# TXB0108PWR.net
KiCad netlist of a schematic drawn in EAGLE
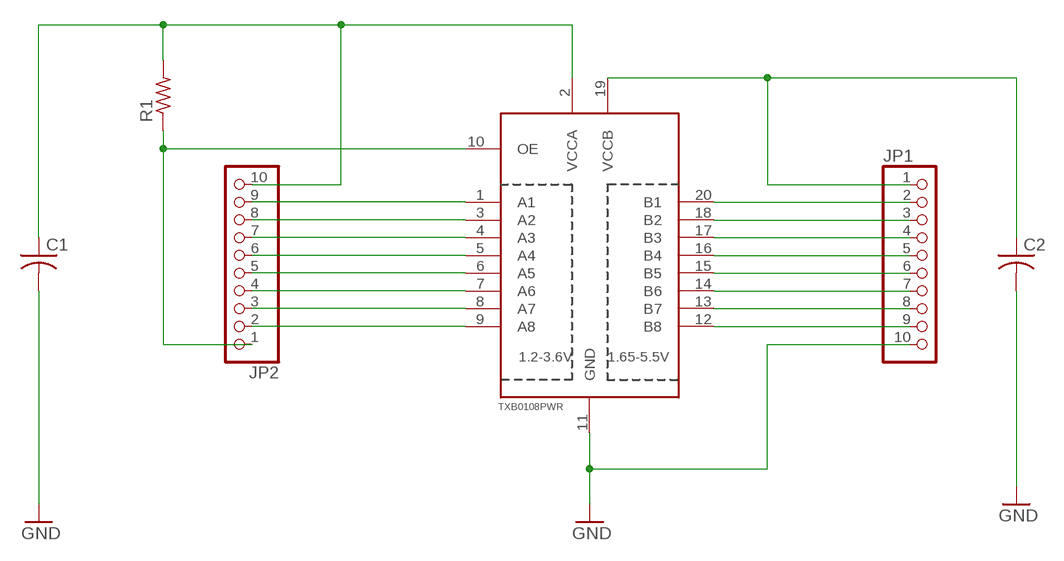
[diagram p0: schematic, sheet 1]

(export (version "E")
  (design (tool "Eeschema 10.0.6"))
  (components
    (comp (ref "C1")
      (value "C-USC0603")
      (footprint "eagle-import:C0603")
      (libsource (lib "eagle-import") (part "C-USC0603"))
    )
    (comp (ref "C2")
      (value "C-USC0603")
      (footprint "eagle-import:C0603")
      (libsource (lib "eagle-import") (part "C-USC0603"))
    )
    (comp (ref "JP1")
      (value "PINHD-1X10")
      (footprint "eagle-import:1X10")
      (libsource (lib "eagle-import") (part "PINHD-1X10"))
    )
    (comp (ref "JP2")
      (value "PINHD-1X10")
      (footprint "eagle-import:1X10")
      (libsource (lib "eagle-import") (part "PINHD-1X10"))
    )
    (comp (ref "R1")
      (value "R-US_R0603")
      (footprint "eagle-import:R0603")
      (libsource (lib "eagle-import") (part "R-US_R0603"))
    )
    (comp (ref "U$1")
      (value "TXB0108PWR")
      (footprint "eagle-import:TXB0108PWR")
      (libsource (lib "eagle-import") (part "TXB0108PWR"))
    )
  )
  (nets
    (net (code "1") (name "GND") (class "Default")
      (node (ref "C1") (pin "2") (pinfunction "2_2") (pintype "passive"))
      (node (ref "C2") (pin "2") (pinfunction "2_2") (pintype "passive"))
      (node (ref "JP1") (pin "10") (pinfunction "10_10") (pintype "passive"))
      (node (ref "U$1") (pin "11") (pinfunction "GND_11") (pintype "bidirectional"))
    )
    (net (code "2") (name "Net-(U$1-A1)") (class "Default")
      (node (ref "JP2") (pin "9") (pinfunction "9_9") (pintype "passive"))
      (node (ref "U$1") (pin "1") (pinfunction "A1_1") (pintype "bidirectional"))
    )
    (net (code "3") (name "Net-(U$1-A2)") (class "Default")
      (node (ref "JP2") (pin "8") (pinfunction "8_8") (pintype "passive"))
      (node (ref "U$1") (pin "3") (pinfunction "A2_3") (pintype "bidirectional"))
    )
    (net (code "4") (name "Net-(U$1-A3)") (class "Default")
      (node (ref "JP2") (pin "7") (pinfunction "7_7") (pintype "passive"))
      (node (ref "U$1") (pin "4") (pinfunction "A3_4") (pintype "bidirectional"))
    )
    (net (code "5") (name "Net-(U$1-A4)") (class "Default")
      (node (ref "JP2") (pin "6") (pinfunction "6_6") (pintype "passive"))
      (node (ref "U$1") (pin "5") (pinfunction "A4_5") (pintype "bidirectional"))
    )
    (net (code "6") (name "Net-(U$1-A5)") (class "Default")
      (node (ref "JP2") (pin "5") (pinfunction "5_5") (pintype "passive"))
      (node (ref "U$1") (pin "6") (pinfunction "A5_6") (pintype "bidirectional"))
    )
    (net (code "7") (name "Net-(U$1-A6)") (class "Default")
      (node (ref "JP2") (pin "4") (pinfunction "4_4") (pintype "passive"))
      (node (ref "U$1") (pin "7") (pinfunction "A6_7") (pintype "bidirectional"))
    )
    (net (code "8") (name "Net-(U$1-A7)") (class "Default")
      (node (ref "JP2") (pin "3") (pinfunction "3_3") (pintype "passive"))
      (node (ref "U$1") (pin "8") (pinfunction "A7_8") (pintype "bidirectional"))
    )
    (net (code "9") (name "Net-(U$1-A8)") (class "Default")
      (node (ref "JP2") (pin "2") (pinfunction "2_2") (pintype "passive"))
      (node (ref "U$1") (pin "9") (pinfunction "A8_9") (pintype "bidirectional"))
    )
    (net (code "10") (name "Net-(U$1-B1)") (class "Default")
      (node (ref "JP1") (pin "2") (pinfunction "2_2") (pintype "passive"))
      (node (ref "U$1") (pin "20") (pinfunction "B1_20") (pintype "bidirectional"))
    )
    (net (code "11") (name "Net-(U$1-B2)") (class "Default")
      (node (ref "JP1") (pin "3") (pinfunction "3_3") (pintype "passive"))
      (node (ref "U$1") (pin "18") (pinfunction "B2_18") (pintype "bidirectional"))
    )
    (net (code "12") (name "Net-(U$1-B3)") (class "Default")
      (node (ref "JP1") (pin "4") (pinfunction "4_4") (pintype "passive"))
      (node (ref "U$1") (pin "17") (pinfunction "B3_17") (pintype "bidirectional"))
    )
    (net (code "13") (name "Net-(U$1-B4)") (class "Default")
      (node (ref "JP1") (pin "5") (pinfunction "5_5") (pintype "passive"))
      (node (ref "U$1") (pin "16") (pinfunction "B4_16") (pintype "bidirectional"))
    )
    (net (code "14") (name "Net-(U$1-B5)") (class "Default")
      (node (ref "JP1") (pin "6") (pinfunction "6_6") (pintype "passive"))
      (node (ref "U$1") (pin "15") (pinfunction "B5_15") (pintype "bidirectional"))
    )
    (net (code "15") (name "Net-(U$1-B6)") (class "Default")
      (node (ref "JP1") (pin "7") (pinfunction "7_7") (pintype "passive"))
      (node (ref "U$1") (pin "14") (pinfunction "B6_14") (pintype "bidirectional"))
    )
    (net (code "16") (name "Net-(U$1-B7)") (class "Default")
      (node (ref "JP1") (pin "8") (pinfunction "8_8") (pintype "passive"))
      (node (ref "U$1") (pin "13") (pinfunction "B7_13") (pintype "bidirectional"))
    )
    (net (code "17") (name "Net-(U$1-B8)") (class "Default")
      (node (ref "JP1") (pin "9") (pinfunction "9_9") (pintype "passive"))
      (node (ref "U$1") (pin "12") (pinfunction "B8_12") (pintype "bidirectional"))
    )
    (net (code "18") (name "Net-(U$1-OE)") (class "Default")
      (node (ref "JP2") (pin "1") (pinfunction "1_1") (pintype "passive"))
      (node (ref "R1") (pin "1") (pinfunction "1_1") (pintype "passive"))
      (node (ref "U$1") (pin "10") (pinfunction "OE_10") (pintype "bidirectional"))
    )
    (net (code "19") (name "Net-(U$1-VCCA)") (class "Default")
      (node (ref "C1") (pin "1") (pinfunction "1_1") (pintype "passive"))
      (node (ref "JP2") (pin "10") (pinfunction "10_10") (pintype "passive"))
      (node (ref "R1") (pin "2") (pinfunction "2_2") (pintype "passive"))
      (node (ref "U$1") (pin "2") (pinfunction "VCCA_2") (pintype "bidirectional"))
    )
    (net (code "20") (name "Net-(U$1-VCCB)") (class "Default")
      (node (ref "C2") (pin "1") (pinfunction "1_1") (pintype "passive"))
      (node (ref "JP1") (pin "1") (pinfunction "1_1") (pintype "passive"))
      (node (ref "U$1") (pin "19") (pinfunction "VCCB_19") (pintype "bidirectional"))
    )
  )
)
